# FMC_and_Power.net
KiCad netlist of a schematic drawn in Altium Designer
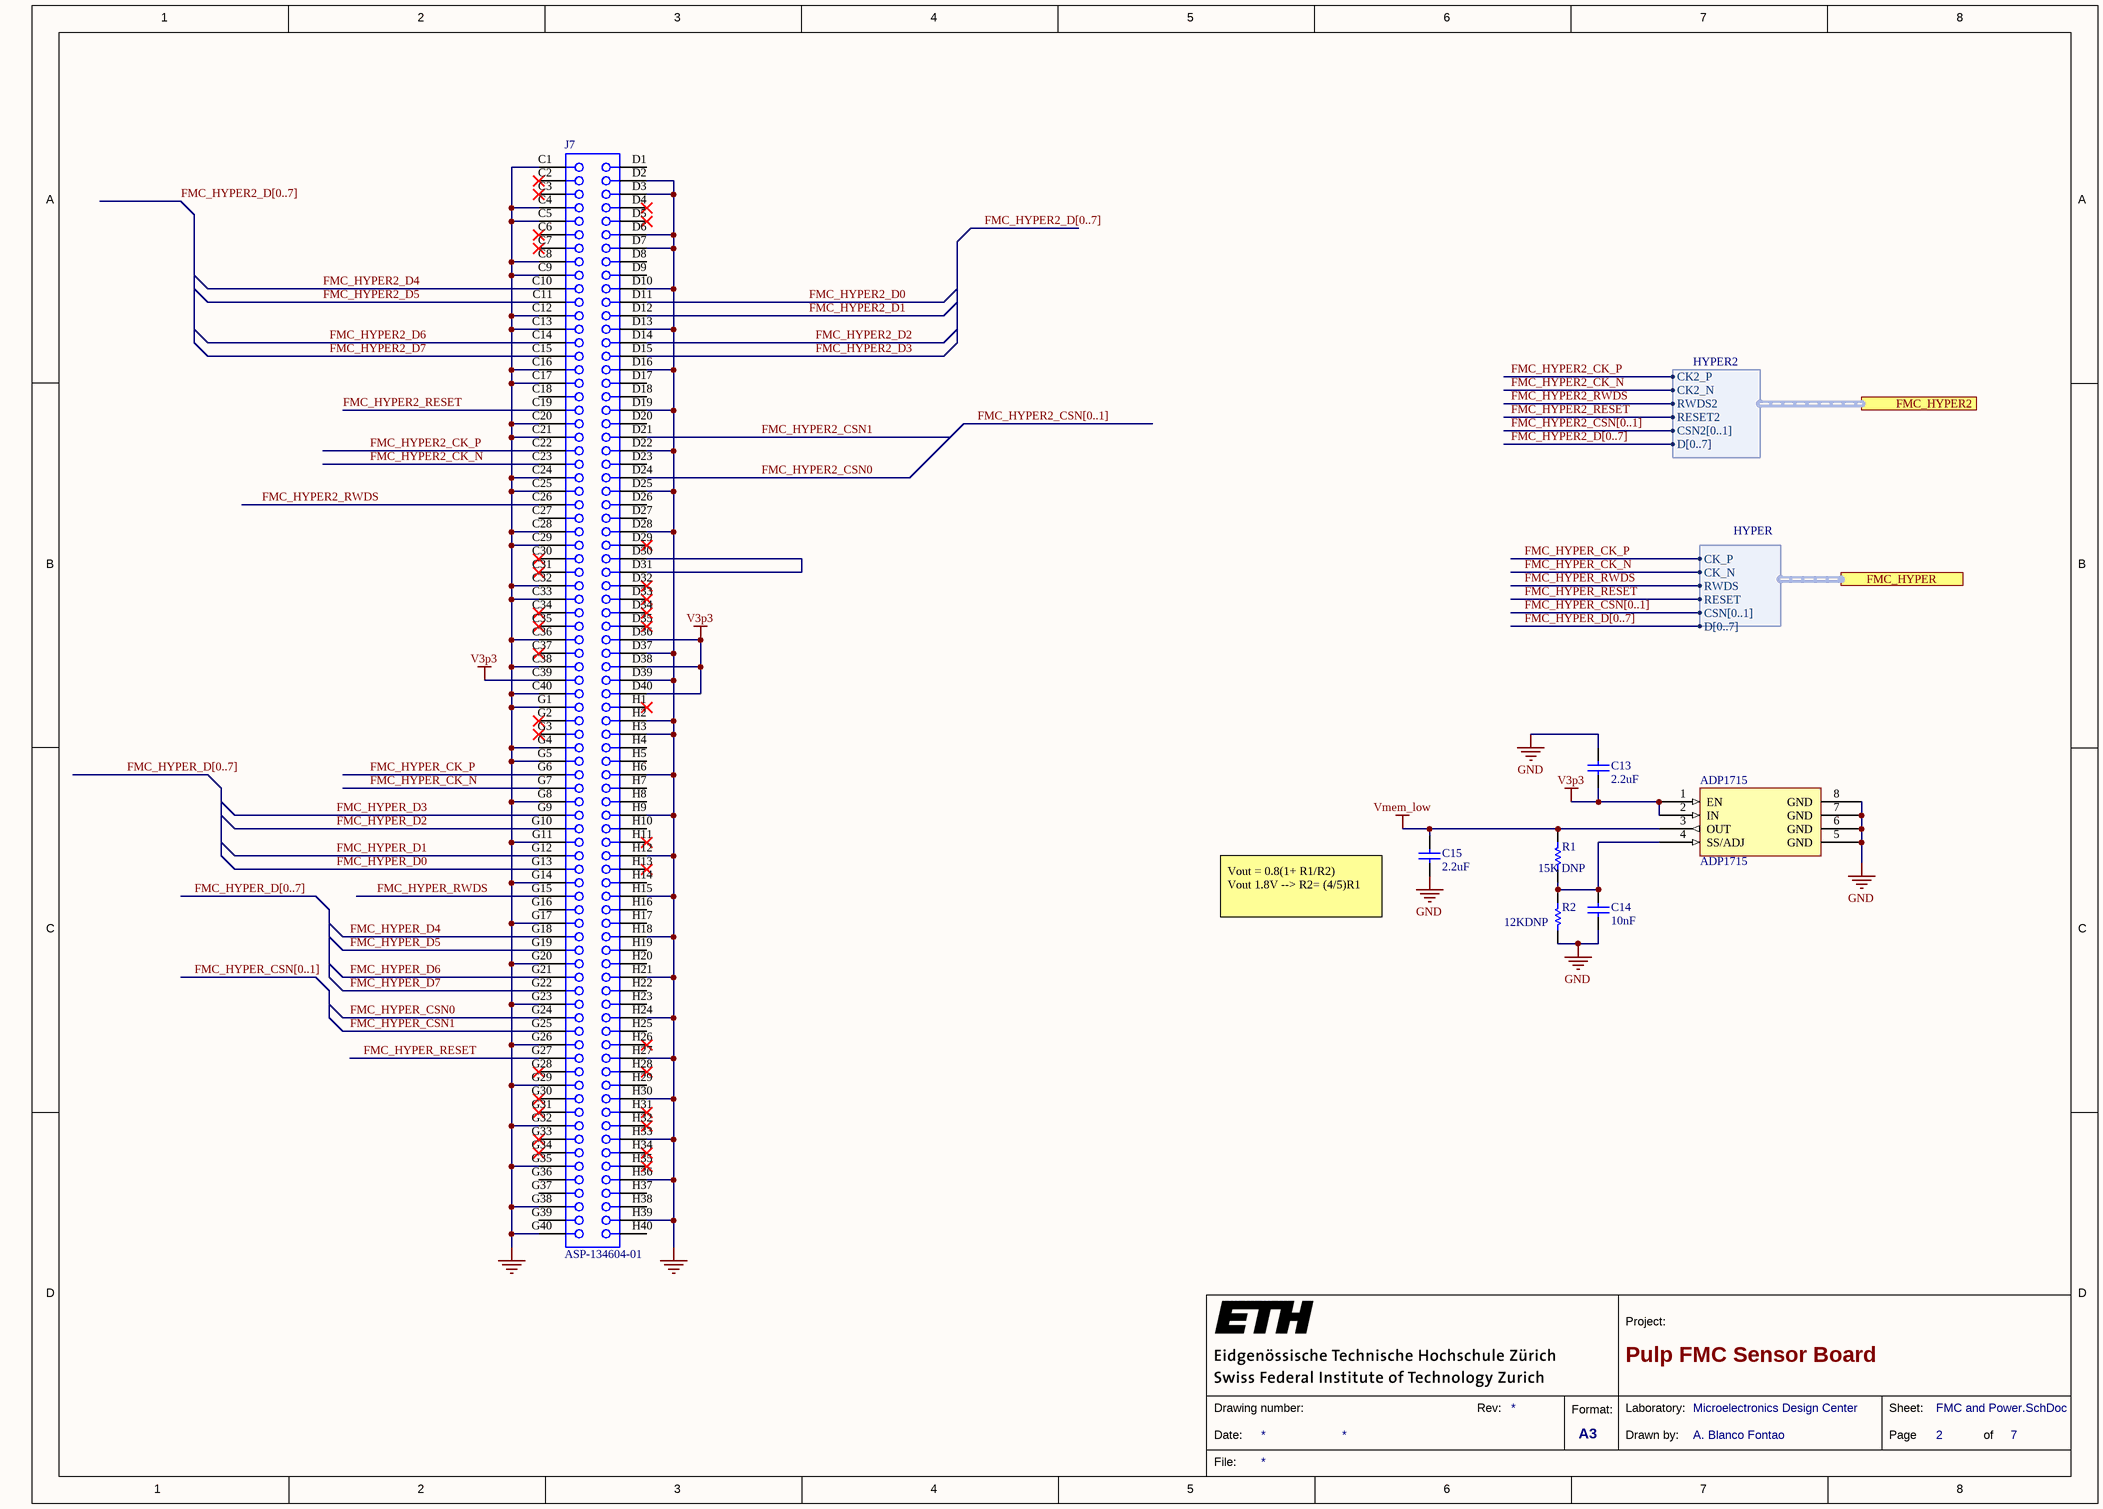
[diagram p0: FMC and Power.SchDoc]

(export (version "E")
  (design (tool "Eeschema 10.0.6"))
  (components
    (comp (ref "ADP1715")
      (value "ADP1715")
      (footprint "TSOP65P490X110-8N")
      (libsource (lib "ADP1715") (part "ADP1715"))
    )
    (comp (ref "C13")
      (value "2.2uF")
      (footprint "CAPC0603(1608)100_N")
      (description "CAP 100nF 25V ±10% 0603 (1608 Metric) Thickness 1mm SMD")
      (fields (field (name "TOLERANCE") "Â±10%") (field (name "Comment") "CAP 100nF 25V 0603(1608)"))
      (libsource (lib "Altium Content Vault") (part "CMP-1035-02588-1"))
    )
    (comp (ref "C14")
      (value "10nF")
      (footprint "CAPC0603(1608)100_N")
      (description "CAP 100nF 25V ±10% 0603 (1608 Metric) Thickness 1mm SMD")
      (fields (field (name "TOLERANCE") "Â±10%") (field (name "Comment") "CAP 100nF 25V 0603(1608)"))
      (libsource (lib "Altium Content Vault") (part "CMP-1035-02588-1"))
    )
    (comp (ref "C15")
      (value "2.2uF")
      (footprint "CAPC0603(1608)100_N")
      (description "CAP 100nF 25V ±10% 0603 (1608 Metric) Thickness 1mm SMD")
      (fields (field (name "TOLERANCE") "Â±10%") (field (name "Comment") "CAP 100nF 25V 0603(1608)"))
      (libsource (lib "Altium Content Vault") (part "CMP-1035-02588-1"))
    )
    (comp (ref "J7")
      (value "ASP-134604-01")
      (footprint "ASP-134604-01")
      (description "Conn Array Terminal FMC Male SKT 160 POS 1.27mm Solder ST SMD")
      (fields (field (name "MANUFACTURER") "Samtec"))
      (libsource (lib "ETHZ Vault") (part "ASP-134604-01"))
    )
    (comp (ref "R1")
      (value "15K DNP")
      (footprint "RESC0603(1608)_N")
      (description "15K 0.1W 5% 0603 (1608 Metric)  SMD")
      (fields (field (name "TOLERANCE") "5 %") (field (name "POWER") "0.1 W"))
      (libsource (lib "Altium Content Vault") (part "CMP-1012-00098-1"))
    )
    (comp (ref "R2")
      (value "12KDNP")
      (footprint "RESC0603(1608)_N")
      (description "12K 0.1W 5% 0603 (1608 Metric)  SMD")
      (fields (field (name "TOLERANCE") "5 %") (field (name "POWER") "0.1 W"))
      (libsource (lib "Altium Content Vault") (part "CMP-1012-00098-1"))
    )
  )
  (nets
    (net (code "3") (name "/FMC_HYPER2_CK_N") (class "Default")
      (node (ref "J7") (pin "C23") (pinfunction "C23_C23") (pintype "passive"))
    )
    (net (code "4") (name "/FMC_HYPER2_CK_P") (class "Default")
      (node (ref "J7") (pin "C22") (pinfunction "C22_C22") (pintype "passive"))
    )
    (net (code "5") (name "/FMC_HYPER2_CSN0") (class "Default")
      (node (ref "J7") (pin "D24") (pinfunction "D24_D24") (pintype "passive"))
    )
    (net (code "6") (name "/FMC_HYPER2_CSN1") (class "Default")
      (node (ref "J7") (pin "D21") (pinfunction "D21_D21") (pintype "passive"))
    )
    (net (code "8") (name "/FMC_HYPER2_D0") (class "Default")
      (node (ref "J7") (pin "D11") (pinfunction "D11_D11") (pintype "passive"))
    )
    (net (code "9") (name "/FMC_HYPER2_D1") (class "Default")
      (node (ref "J7") (pin "D12") (pinfunction "D12_D12") (pintype "passive"))
    )
    (net (code "10") (name "/FMC_HYPER2_D2") (class "Default")
      (node (ref "J7") (pin "D14") (pinfunction "D14_D14") (pintype "passive"))
    )
    (net (code "11") (name "/FMC_HYPER2_D3") (class "Default")
      (node (ref "J7") (pin "D15") (pinfunction "D15_D15") (pintype "passive"))
    )
    (net (code "12") (name "/FMC_HYPER2_D4") (class "Default")
      (node (ref "J7") (pin "C10") (pinfunction "C10_C10") (pintype "passive"))
    )
    (net (code "13") (name "/FMC_HYPER2_D5") (class "Default")
      (node (ref "J7") (pin "C11") (pinfunction "C11_C11") (pintype "passive"))
    )
    (net (code "14") (name "/FMC_HYPER2_D6") (class "Default")
      (node (ref "J7") (pin "C14") (pinfunction "C14_C14") (pintype "passive"))
    )
    (net (code "15") (name "/FMC_HYPER2_D7") (class "Default")
      (node (ref "J7") (pin "C15") (pinfunction "C15_C15") (pintype "passive"))
    )
    (net (code "17") (name "/FMC_HYPER2_RESET") (class "Default")
      (node (ref "J7") (pin "C19") (pinfunction "C19_C19") (pintype "passive"))
    )
    (net (code "18") (name "/FMC_HYPER2_RWDS") (class "Default")
      (node (ref "J7") (pin "C26") (pinfunction "C26_C26") (pintype "passive"))
    )
    (net (code "20") (name "/FMC_HYPER_CK_N") (class "Default")
      (node (ref "J7") (pin "G7") (pinfunction "G7_G7") (pintype "passive"))
    )
    (net (code "21") (name "/FMC_HYPER_CK_P") (class "Default")
      (node (ref "J7") (pin "G6") (pinfunction "G6_G6") (pintype "passive"))
    )
    (net (code "22") (name "/FMC_HYPER_CSN0") (class "Default")
      (node (ref "J7") (pin "G24") (pinfunction "G24_G24") (pintype "passive"))
    )
    (net (code "23") (name "/FMC_HYPER_CSN1") (class "Default")
      (node (ref "J7") (pin "G25") (pinfunction "G25_G25") (pintype "passive"))
    )
    (net (code "25") (name "/FMC_HYPER_D0") (class "Default")
      (node (ref "J7") (pin "G13") (pinfunction "G13_G13") (pintype "passive"))
    )
    (net (code "26") (name "/FMC_HYPER_D1") (class "Default")
      (node (ref "J7") (pin "G12") (pinfunction "G12_G12") (pintype "passive"))
    )
    (net (code "27") (name "/FMC_HYPER_D2") (class "Default")
      (node (ref "J7") (pin "G10") (pinfunction "G10_G10") (pintype "passive"))
    )
    (net (code "28") (name "/FMC_HYPER_D3") (class "Default")
      (node (ref "J7") (pin "G9") (pinfunction "G9_G9") (pintype "passive"))
    )
    (net (code "29") (name "/FMC_HYPER_D4") (class "Default")
      (node (ref "J7") (pin "G18") (pinfunction "G18_G18") (pintype "passive"))
    )
    (net (code "30") (name "/FMC_HYPER_D5") (class "Default")
      (node (ref "J7") (pin "G19") (pinfunction "G19_G19") (pintype "passive"))
    )
    (net (code "31") (name "/FMC_HYPER_D6") (class "Default")
      (node (ref "J7") (pin "G21") (pinfunction "G21_G21") (pintype "passive"))
    )
    (net (code "32") (name "/FMC_HYPER_D7") (class "Default")
      (node (ref "J7") (pin "G22") (pinfunction "G22_G22") (pintype "passive"))
    )
    (net (code "34") (name "/FMC_HYPER_RESET") (class "Default")
      (node (ref "J7") (pin "G27") (pinfunction "G27_G27") (pintype "passive"))
    )
    (net (code "35") (name "/FMC_HYPER_RWDS") (class "Default")
      (node (ref "J7") (pin "G15") (pinfunction "G15_G15") (pintype "passive"))
    )
    (net (code "39") (name "GND") (class "Default")
      (node (ref "ADP1715") (pin "5") (pinfunction "GND_5") (pintype "power_in"))
      (node (ref "ADP1715") (pin "6") (pinfunction "GND_6") (pintype "power_in"))
      (node (ref "ADP1715") (pin "7") (pinfunction "GND_7") (pintype "power_in"))
      (node (ref "ADP1715") (pin "8") (pinfunction "GND_8") (pintype "power_in"))
      (node (ref "C13") (pin "2") (pinfunction "2_2") (pintype "passive"))
      (node (ref "C14") (pin "1") (pinfunction "1_1") (pintype "passive"))
      (node (ref "C15") (pin "1") (pinfunction "1_1") (pintype "passive"))
      (node (ref "J7") (pin "C1") (pinfunction "C1_C1") (pintype "passive"))
      (node (ref "J7") (pin "C12") (pinfunction "C12_C12") (pintype "passive"))
      (node (ref "J7") (pin "C13") (pinfunction "C13_C13") (pintype "passive"))
      (node (ref "J7") (pin "C16") (pinfunction "C16_C16") (pintype "passive"))
      (node (ref "J7") (pin "C17") (pinfunction "C17_C17") (pintype "passive"))
      (node (ref "J7") (pin "C20") (pinfunction "C20_C20") (pintype "passive"))
      (node (ref "J7") (pin "C21") (pinfunction "C21_C21") (pintype "passive"))
      (node (ref "J7") (pin "C24") (pinfunction "C24_C24") (pintype "passive"))
      (node (ref "J7") (pin "C25") (pinfunction "C25_C25") (pintype "passive"))
      (node (ref "J7") (pin "C28") (pinfunction "C28_C28") (pintype "passive"))
      (node (ref "J7") (pin "C29") (pinfunction "C29_C29") (pintype "passive"))
      (node (ref "J7") (pin "C32") (pinfunction "C32_C32") (pintype "passive"))
      (node (ref "J7") (pin "C33") (pinfunction "C33_C33") (pintype "passive"))
      (node (ref "J7") (pin "C36") (pinfunction "C36_C36") (pintype "passive"))
      (node (ref "J7") (pin "C38") (pinfunction "C38_C38") (pintype "passive"))
      (node (ref "J7") (pin "C4") (pinfunction "C4_C4") (pintype "passive"))
      (node (ref "J7") (pin "C40") (pinfunction "C40_C40") (pintype "passive"))
      (node (ref "J7") (pin "C5") (pinfunction "C5_C5") (pintype "passive"))
      (node (ref "J7") (pin "C8") (pinfunction "C8_C8") (pintype "passive"))
      (node (ref "J7") (pin "C9") (pinfunction "C9_C9") (pintype "passive"))
      (node (ref "J7") (pin "D10") (pinfunction "D10_D10") (pintype "passive"))
      (node (ref "J7") (pin "D13") (pinfunction "D13_D13") (pintype "passive"))
      (node (ref "J7") (pin "D16") (pinfunction "D16_D16") (pintype "passive"))
      (node (ref "J7") (pin "D19") (pinfunction "D19_D19") (pintype "passive"))
      (node (ref "J7") (pin "D2") (pinfunction "D2_D2") (pintype "passive"))
      (node (ref "J7") (pin "D22") (pinfunction "D22_D22") (pintype "passive"))
      (node (ref "J7") (pin "D25") (pinfunction "D25_D25") (pintype "passive"))
      (node (ref "J7") (pin "D28") (pinfunction "D28_D28") (pintype "passive"))
      (node (ref "J7") (pin "D3") (pinfunction "D3_D3") (pintype "passive"))
      (node (ref "J7") (pin "D37") (pinfunction "D37_D37") (pintype "passive"))
      (node (ref "J7") (pin "D39") (pinfunction "D39_D39") (pintype "passive"))
      (node (ref "J7") (pin "D6") (pinfunction "D6_D6") (pintype "passive"))
      (node (ref "J7") (pin "D7") (pinfunction "D7_D7") (pintype "passive"))
      (node (ref "J7") (pin "G1") (pinfunction "G1_G1") (pintype "passive"))
      (node (ref "J7") (pin "G11") (pinfunction "G11_G11") (pintype "passive"))
      (node (ref "J7") (pin "G14") (pinfunction "G14_G14") (pintype "passive"))
      (node (ref "J7") (pin "G17") (pinfunction "G17_G17") (pintype "passive"))
      (node (ref "J7") (pin "G20") (pinfunction "G20_G20") (pintype "passive"))
      (node (ref "J7") (pin "G23") (pinfunction "G23_G23") (pintype "passive"))
      (node (ref "J7") (pin "G26") (pinfunction "G26_G26") (pintype "passive"))
      (node (ref "J7") (pin "G29") (pinfunction "G29_G29") (pintype "passive"))
      (node (ref "J7") (pin "G32") (pinfunction "G32_G32") (pintype "passive"))
      (node (ref "J7") (pin "G35") (pinfunction "G35_G35") (pintype "passive"))
      (node (ref "J7") (pin "G38") (pinfunction "G38_G38") (pintype "passive"))
      (node (ref "J7") (pin "G4") (pinfunction "G4_G4") (pintype "passive"))
      (node (ref "J7") (pin "G40") (pinfunction "G40_G40") (pintype "passive"))
      (node (ref "J7") (pin "G5") (pinfunction "G5_G5") (pintype "passive"))
      (node (ref "J7") (pin "G8") (pinfunction "G8_G8") (pintype "passive"))
      (node (ref "J7") (pin "H12") (pinfunction "H12_H12") (pintype "passive"))
      (node (ref "J7") (pin "H15") (pinfunction "H15_H15") (pintype "passive"))
      (node (ref "J7") (pin "H18") (pinfunction "H18_H18") (pintype "passive"))
      (node (ref "J7") (pin "H2") (pinfunction "H2_H2") (pintype "passive"))
      (node (ref "J7") (pin "H21") (pinfunction "H21_H21") (pintype "passive"))
      (node (ref "J7") (pin "H24") (pinfunction "H24_H24") (pintype "passive"))
      (node (ref "J7") (pin "H27") (pinfunction "H27_H27") (pintype "passive"))
      (node (ref "J7") (pin "H3") (pinfunction "H3_H3") (pintype "passive"))
      (node (ref "J7") (pin "H30") (pinfunction "H30_H30") (pintype "passive"))
      (node (ref "J7") (pin "H33") (pinfunction "H33_H33") (pintype "passive"))
      (node (ref "J7") (pin "H36") (pinfunction "H36_H36") (pintype "passive"))
      (node (ref "J7") (pin "H39") (pinfunction "H39_H39") (pintype "passive"))
      (node (ref "J7") (pin "H6") (pinfunction "H6_H6") (pintype "passive"))
      (node (ref "J7") (pin "H9") (pinfunction "H9_H9") (pintype "passive"))
      (node (ref "R2") (pin "1") (pinfunction "1_1") (pintype "passive"))
    )
    (net (code "40") (name "Net-(ADP1715-SS{slash}ADJ)") (class "Default")
      (node (ref "ADP1715") (pin "4") (pinfunction "SS/ADJ_4") (pintype "input"))
      (node (ref "C14") (pin "2") (pinfunction "2_2") (pintype "passive"))
      (node (ref "R1") (pin "1") (pinfunction "1_1") (pintype "passive"))
      (node (ref "R2") (pin "2") (pinfunction "2_2") (pintype "passive"))
    )
    (net (code "41") (name "Net-(J7-PadD30)") (class "Default")
      (node (ref "J7") (pin "D30") (pinfunction "D30_D30") (pintype "passive"))
      (node (ref "J7") (pin "D31") (pinfunction "D31_D31") (pintype "passive"))
    )
    (net (code "42") (name "V3p3") (class "Default")
      (node (ref "ADP1715") (pin "1") (pinfunction "EN_1") (pintype "input"))
      (node (ref "ADP1715") (pin "2") (pinfunction "IN_2") (pintype "input"))
      (node (ref "C13") (pin "1") (pinfunction "1_1") (pintype "passive"))
      (node (ref "J7") (pin "C39") (pinfunction "C39_C39") (pintype "passive"))
      (node (ref "J7") (pin "D36") (pinfunction "D36_D36") (pintype "passive"))
      (node (ref "J7") (pin "D38") (pinfunction "D38_D38") (pintype "passive"))
      (node (ref "J7") (pin "D40") (pinfunction "D40_D40") (pintype "passive"))
    )
    (net (code "43") (name "Vmem_low") (class "Default")
      (node (ref "ADP1715") (pin "3") (pinfunction "OUT_3") (pintype "output"))
      (node (ref "C15") (pin "2") (pinfunction "2_2") (pintype "passive"))
      (node (ref "R1") (pin "2") (pinfunction "2_2") (pintype "passive"))
    )
    (net (code "44") (name "unconnected-(J7-PadC2)") (class "Default")
      (node (ref "J7") (pin "C2") (pinfunction "C2_C2") (pintype "passive+no_connect"))
    )
    (net (code "45") (name "unconnected-(J7-PadC3)") (class "Default")
      (node (ref "J7") (pin "C3") (pinfunction "C3_C3") (pintype "passive+no_connect"))
    )
    (net (code "46") (name "unconnected-(J7-PadC6)") (class "Default")
      (node (ref "J7") (pin "C6") (pinfunction "C6_C6") (pintype "passive+no_connect"))
    )
    (net (code "47") (name "unconnected-(J7-PadC7)") (class "Default")
      (node (ref "J7") (pin "C7") (pinfunction "C7_C7") (pintype "passive+no_connect"))
    )
    (net (code "48") (name "unconnected-(J7-PadC18)") (class "Default")
      (node (ref "J7") (pin "C18") (pinfunction "C18_C18") (pintype "passive"))
    )
    (net (code "49") (name "unconnected-(J7-PadC27)") (class "Default")
      (node (ref "J7") (pin "C27") (pinfunction "C27_C27") (pintype "passive"))
    )
    (net (code "50") (name "unconnected-(J7-PadC30)") (class "Default")
      (node (ref "J7") (pin "C30") (pinfunction "C30_C30") (pintype "passive+no_connect"))
    )
    (net (code "51") (name "unconnected-(J7-PadC31)") (class "Default")
      (node (ref "J7") (pin "C31") (pinfunction "C31_C31") (pintype "passive+no_connect"))
    )
    (net (code "52") (name "unconnected-(J7-PadC34)") (class "Default")
      (node (ref "J7") (pin "C34") (pinfunction "C34_C34") (pintype "passive+no_connect"))
    )
    (net (code "53") (name "unconnected-(J7-PadC35)") (class "Default")
      (node (ref "J7") (pin "C35") (pinfunction "C35_C35") (pintype "passive+no_connect"))
    )
    (net (code "54") (name "unconnected-(J7-PadC37)") (class "Default")
      (node (ref "J7") (pin "C37") (pinfunction "C37_C37") (pintype "passive+no_connect"))
    )
    (net (code "55") (name "unconnected-(J7-PadD1)") (class "Default")
      (node (ref "J7") (pin "D1") (pinfunction "D1_D1") (pintype "passive"))
    )
    (net (code "56") (name "unconnected-(J7-PadD4)") (class "Default")
      (node (ref "J7") (pin "D4") (pinfunction "D4_D4") (pintype "passive+no_connect"))
    )
    (net (code "57") (name "unconnected-(J7-PadD5)") (class "Default")
      (node (ref "J7") (pin "D5") (pinfunction "D5_D5") (pintype "passive+no_connect"))
    )
    (net (code "58") (name "unconnected-(J7-PadD8)") (class "Default")
      (node (ref "J7") (pin "D8") (pinfunction "D8_D8") (pintype "passive"))
    )
    (net (code "59") (name "unconnected-(J7-PadD9)") (class "Default")
      (node (ref "J7") (pin "D9") (pinfunction "D9_D9") (pintype "passive"))
    )
    (net (code "60") (name "unconnected-(J7-PadD17)") (class "Default")
      (node (ref "J7") (pin "D17") (pinfunction "D17_D17") (pintype "passive"))
    )
    (net (code "61") (name "unconnected-(J7-PadD18)") (class "Default")
      (node (ref "J7") (pin "D18") (pinfunction "D18_D18") (pintype "passive"))
    )
    (net (code "62") (name "unconnected-(J7-PadD20)") (class "Default")
      (node (ref "J7") (pin "D20") (pinfunction "D20_D20") (pintype "passive"))
    )
    (net (code "63") (name "unconnected-(J7-PadD23)") (class "Default")
      (node (ref "J7") (pin "D23") (pinfunction "D23_D23") (pintype "passive"))
    )
    (net (code "64") (name "unconnected-(J7-PadD26)") (class "Default")
      (node (ref "J7") (pin "D26") (pinfunction "D26_D26") (pintype "passive"))
    )
    (net (code "65") (name "unconnected-(J7-PadD27)") (class "Default")
      (node (ref "J7") (pin "D27") (pinfunction "D27_D27") (pintype "passive"))
    )
    (net (code "66") (name "unconnected-(J7-PadD29)") (class "Default")
      (node (ref "J7") (pin "D29") (pinfunction "D29_D29") (pintype "passive+no_connect"))
    )
    (net (code "67") (name "unconnected-(J7-PadD32)") (class "Default")
      (node (ref "J7") (pin "D32") (pinfunction "D32_D32") (pintype "passive+no_connect"))
    )
    (net (code "68") (name "unconnected-(J7-PadD33)") (class "Default")
      (node (ref "J7") (pin "D33") (pinfunction "D33_D33") (pintype "passive+no_connect"))
    )
    (net (code "69") (name "unconnected-(J7-PadD34)") (class "Default")
      (node (ref "J7") (pin "D34") (pinfunction "D34_D34") (pintype "passive+no_connect"))
    )
    (net (code "70") (name "unconnected-(J7-PadD35)") (class "Default")
      (node (ref "J7") (pin "D35") (pinfunction "D35_D35") (pintype "passive+no_connect"))
    )
    (net (code "71") (name "unconnected-(J7-PadG2)") (class "Default")
      (node (ref "J7") (pin "G2") (pinfunction "G2_G2") (pintype "passive+no_connect"))
    )
    (net (code "72") (name "unconnected-(J7-PadG3)") (class "Default")
      (node (ref "J7") (pin "G3") (pinfunction "G3_G3") (pintype "passive+no_connect"))
    )
    (net (code "73") (name "unconnected-(J7-PadG16)") (class "Default")
      (node (ref "J7") (pin "G16") (pinfunction "G16_G16") (pintype "passive"))
    )
    (net (code "74") (name "unconnected-(J7-PadG28)") (class "Default")
      (node (ref "J7") (pin "G28") (pinfunction "G28_G28") (pintype "passive+no_connect"))
    )
    (net (code "75") (name "unconnected-(J7-PadG30)") (class "Default")
      (node (ref "J7") (pin "G30") (pinfunction "G30_G30") (pintype "passive+no_connect"))
    )
    (net (code "76") (name "unconnected-(J7-PadG31)") (class "Default")
      (node (ref "J7") (pin "G31") (pinfunction "G31_G31") (pintype "passive+no_connect"))
    )
    (net (code "77") (name "unconnected-(J7-PadG33)") (class "Default")
      (node (ref "J7") (pin "G33") (pinfunction "G33_G33") (pintype "passive+no_connect"))
    )
    (net (code "78") (name "unconnected-(J7-PadG34)") (class "Default")
      (node (ref "J7") (pin "G34") (pinfunction "G34_G34") (pintype "passive+no_connect"))
    )
    (net (code "79") (name "unconnected-(J7-PadG36)") (class "Default")
      (node (ref "J7") (pin "G36") (pinfunction "G36_G36") (pintype "passive"))
    )
    (net (code "80") (name "unconnected-(J7-PadG37)") (class "Default")
      (node (ref "J7") (pin "G37") (pinfunction "G37_G37") (pintype "passive"))
    )
    (net (code "81") (name "unconnected-(J7-PadG39)") (class "Default")
      (node (ref "J7") (pin "G39") (pinfunction "G39_G39") (pintype "passive"))
    )
    (net (code "82") (name "unconnected-(J7-PadH1)") (class "Default")
      (node (ref "J7") (pin "H1") (pinfunction "H1_H1") (pintype "passive+no_connect"))
    )
    (net (code "83") (name "unconnected-(J7-PadH4)") (class "Default")
      (node (ref "J7") (pin "H4") (pinfunction "H4_H4") (pintype "passive"))
    )
    (net (code "84") (name "unconnected-(J7-PadH5)") (class "Default")
      (node (ref "J7") (pin "H5") (pinfunction "H5_H5") (pintype "passive"))
    )
    (net (code "85") (name "unconnected-(J7-PadH7)") (class "Default")
      (node (ref "J7") (pin "H7") (pinfunction "H7_H7") (pintype "passive"))
    )
    (net (code "86") (name "unconnected-(J7-PadH8)") (class "Default")
      (node (ref "J7") (pin "H8") (pinfunction "H8_H8") (pintype "passive"))
    )
    (net (code "87") (name "unconnected-(J7-PadH10)") (class "Default")
      (node (ref "J7") (pin "H10") (pinfunction "H10_H10") (pintype "passive"))
    )
    (net (code "88") (name "unconnected-(J7-PadH11)") (class "Default")
      (node (ref "J7") (pin "H11") (pinfunction "H11_H11") (pintype "passive+no_connect"))
    )
    (net (code "89") (name "unconnected-(J7-PadH13)") (class "Default")
      (node (ref "J7") (pin "H13") (pinfunction "H13_H13") (pintype "passive+no_connect"))
    )
    (net (code "90") (name "unconnected-(J7-PadH14)") (class "Default")
      (node (ref "J7") (pin "H14") (pinfunction "H14_H14") (pintype "passive"))
    )
    (net (code "91") (name "unconnected-(J7-PadH16)") (class "Default")
      (node (ref "J7") (pin "H16") (pinfunction "H16_H16") (pintype "passive"))
    )
    (net (code "92") (name "unconnected-(J7-PadH17)") (class "Default")
      (node (ref "J7") (pin "H17") (pinfunction "H17_H17") (pintype "passive"))
    )
    (net (code "93") (name "unconnected-(J7-PadH19)") (class "Default")
      (node (ref "J7") (pin "H19") (pinfunction "H19_H19") (pintype "passive"))
    )
    (net (code "94") (name "unconnected-(J7-PadH20)") (class "Default")
      (node (ref "J7") (pin "H20") (pinfunction "H20_H20") (pintype "passive"))
    )
    (net (code "95") (name "unconnected-(J7-PadH22)") (class "Default")
      (node (ref "J7") (pin "H22") (pinfunction "H22_H22") (pintype "passive"))
    )
    (net (code "96") (name "unconnected-(J7-PadH23)") (class "Default")
      (node (ref "J7") (pin "H23") (pinfunction "H23_H23") (pintype "passive"))
    )
    (net (code "97") (name "unconnected-(J7-PadH25)") (class "Default")
      (node (ref "J7") (pin "H25") (pinfunction "H25_H25") (pintype "passive"))
    )
    (net (code "98") (name "unconnected-(J7-PadH26)") (class "Default")
      (node (ref "J7") (pin "H26") (pinfunction "H26_H26") (pintype "passive+no_connect"))
    )
    (net (code "99") (name "unconnected-(J7-PadH28)") (class "Default")
      (node (ref "J7") (pin "H28") (pinfunction "H28_H28") (pintype "passive+no_connect"))
    )
    (net (code "100") (name "unconnected-(J7-PadH29)") (class "Default")
      (node (ref "J7") (pin "H29") (pinfunction "H29_H29") (pintype "passive"))
    )
    (net (code "101") (name "unconnected-(J7-PadH31)") (class "Default")
      (node (ref "J7") (pin "H31") (pinfunction "H31_H31") (pintype "passive+no_connect"))
    )
    (net (code "102") (name "unconnected-(J7-PadH32)") (class "Default")
      (node (ref "J7") (pin "H32") (pinfunction "H32_H32") (pintype "passive+no_connect"))
    )
    (net (code "103") (name "unconnected-(J7-PadH34)") (class "Default")
      (node (ref "J7") (pin "H34") (pinfunction "H34_H34") (pintype "passive+no_connect"))
    )
    (net (code "104") (name "unconnected-(J7-PadH35)") (class "Default")
      (node (ref "J7") (pin "H35") (pinfunction "H35_H35") (pintype "passive+no_connect"))
    )
    (net (code "105") (name "unconnected-(J7-PadH37)") (class "Default")
      (node (ref "J7") (pin "H37") (pinfunction "H37_H37") (pintype "passive"))
    )
    (net (code "106") (name "unconnected-(J7-PadH38)") (class "Default")
      (node (ref "J7") (pin "H38") (pinfunction "H38_H38") (pintype "passive"))
    )
    (net (code "107") (name "unconnected-(J7-PadH40)") (class "Default")
      (node (ref "J7") (pin "H40") (pinfunction "H40_H40") (pintype "passive"))
    )
  )
)
